# arduino_aprs_modem_-_corrected.net
KiCad netlist of a schematic drawn in EAGLE
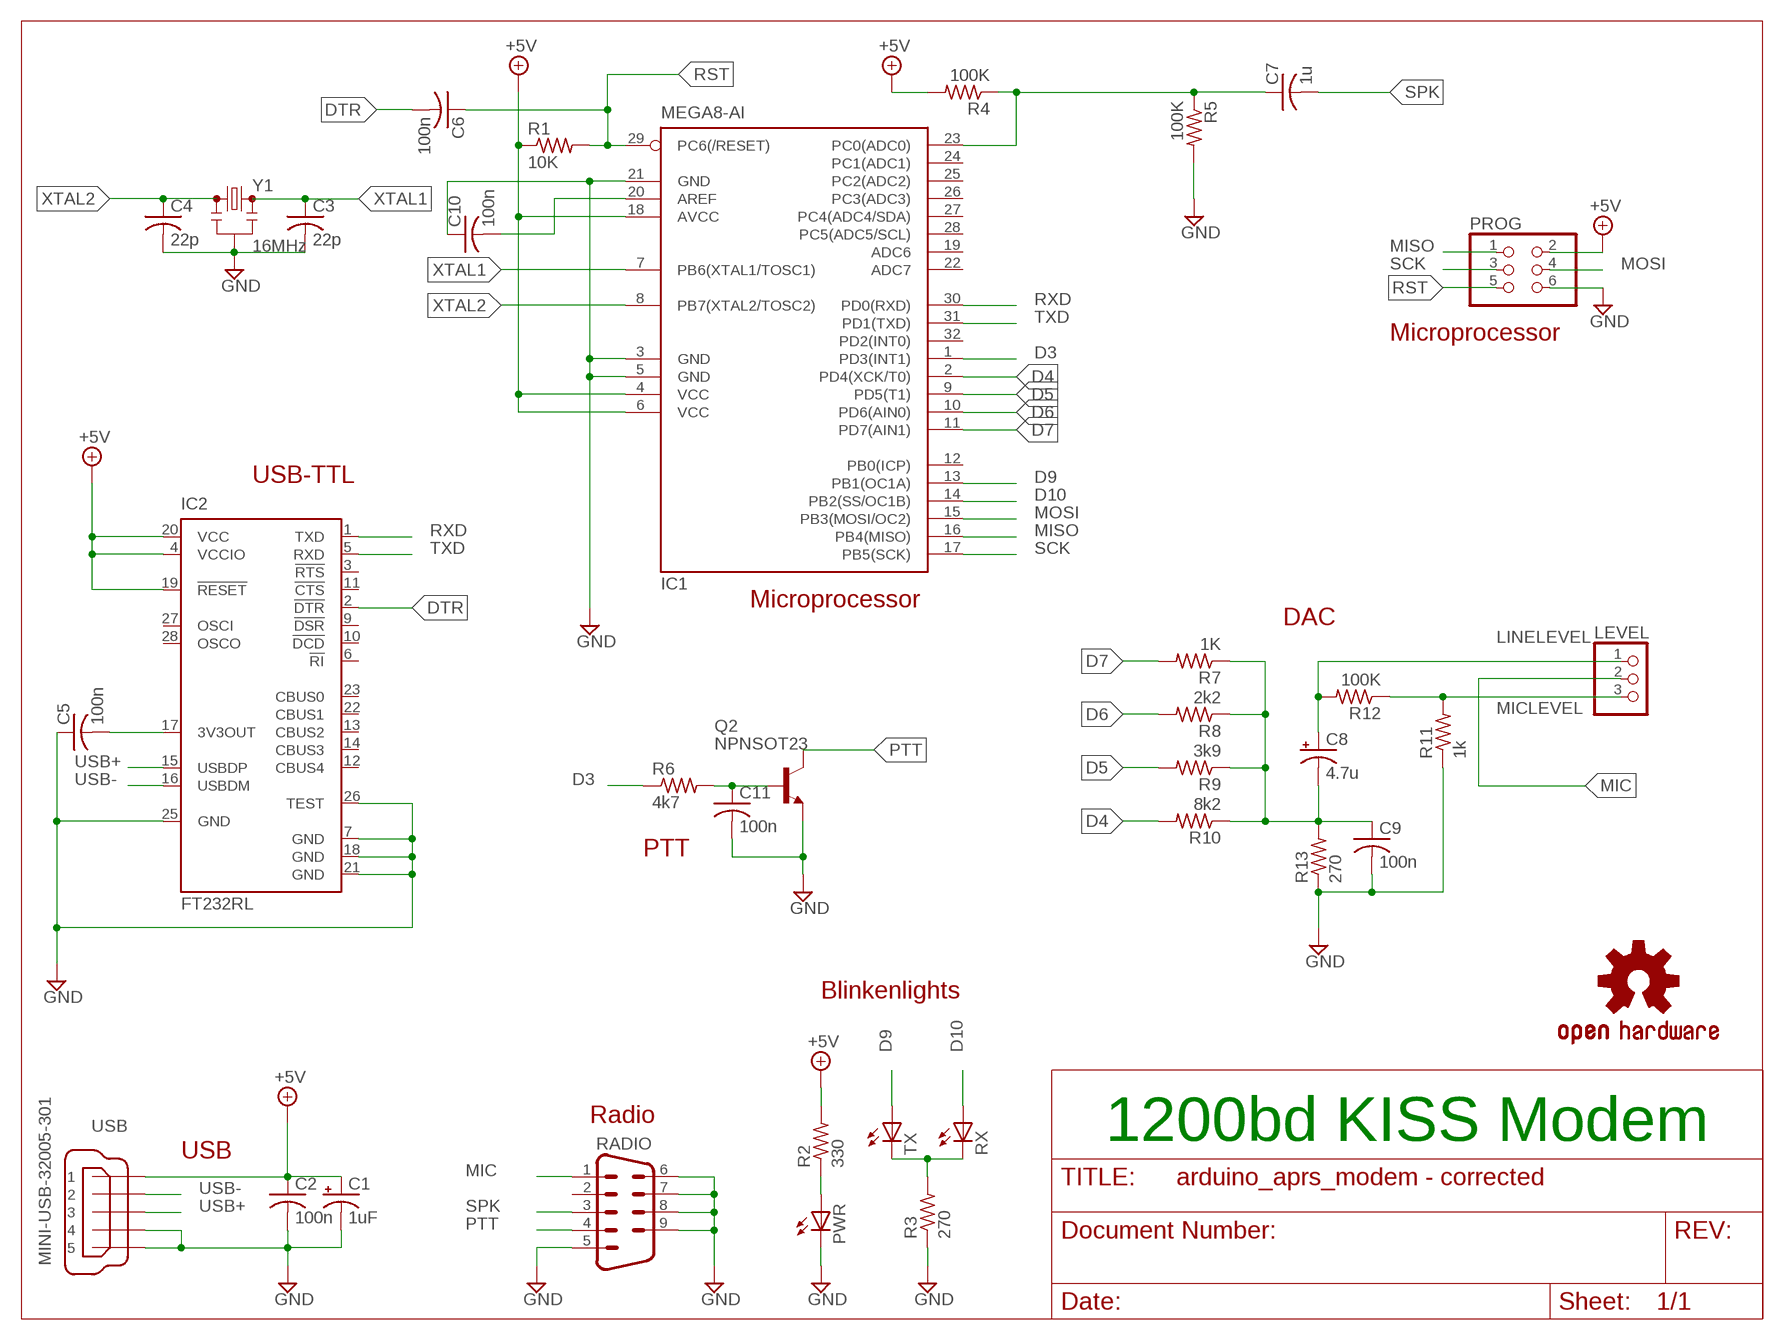
[diagram p0: schematic, sheet 1]

(export (version "E")
  (design (tool "Eeschema 10.0.6"))
  (components
    (comp (ref "C1")
      (value "1uF")
      (footprint "eagle-import:E2-5")
      (libsource (lib "eagle-import") (part "CPOL-USE2-5"))
    )
    (comp (ref "C2")
      (value "100n")
      (footprint "eagle-import:C0805")
      (libsource (lib "eagle-import") (part "C-USC0805"))
    )
    (comp (ref "C3")
      (value "22p")
      (footprint "eagle-import:C0805")
      (libsource (lib "eagle-import") (part "C-USC0805"))
    )
    (comp (ref "C4")
      (value "22p")
      (footprint "eagle-import:C0805")
      (libsource (lib "eagle-import") (part "C-USC0805"))
    )
    (comp (ref "C5")
      (value "100n")
      (footprint "eagle-import:C0805")
      (libsource (lib "eagle-import") (part "C-USC0805"))
    )
    (comp (ref "C6")
      (value "100n")
      (footprint "eagle-import:C0805")
      (libsource (lib "eagle-import") (part "C-USC0805"))
    )
    (comp (ref "C7")
      (value "1u")
      (footprint "eagle-import:C0805")
      (libsource (lib "eagle-import") (part "C-USC0805"))
    )
    (comp (ref "C8")
      (value "4.7u")
      (footprint "eagle-import:E2-5")
      (libsource (lib "eagle-import") (part "CPOL-USE2-5"))
    )
    (comp (ref "C9")
      (value "100n")
      (footprint "eagle-import:C0805")
      (libsource (lib "eagle-import") (part "C-USC0805"))
    )
    (comp (ref "C10")
      (value "100n")
      (footprint "eagle-import:C0805")
      (libsource (lib "eagle-import") (part "C-USC0805"))
    )
    (comp (ref "C11")
      (value "100n")
      (footprint "eagle-import:C0805")
      (libsource (lib "eagle-import") (part "C-USC0805"))
    )
    (comp (ref "IC1")
      (value "MEGA8-AI")
      (footprint "eagle-import:TQFP32-08")
      (fields (field (name "MPN") "ATMEGA8-16AU"))
      (libsource (lib "eagle-import") (part "MEGA8-AI"))
    )
    (comp (ref "IC2")
      (value "FT232RL")
      (footprint "eagle-import:SSOP28")
      (libsource (lib "eagle-import") (part "FT232RL"))
    )
    (comp (ref "LEVEL")
      (value "PINHD-1X3")
      (footprint "eagle-import:1X03")
      (libsource (lib "eagle-import") (part "PINHD-1X3"))
    )
    (comp (ref "PROG")
      (value "PINHD-2X3")
      (footprint "eagle-import:2X03")
      (libsource (lib "eagle-import") (part "PINHD-2X3"))
    )
    (comp (ref "PWR")
      (value "LEDCHIPLED_0805")
      (footprint "eagle-import:CHIPLED_0805")
      (libsource (lib "eagle-import") (part "LEDCHIPLED_0805"))
    )
    (comp (ref "Q2")
      (value "NPNSOT23")
      (footprint "eagle-import:SOT23")
      (libsource (lib "eagle-import") (part "NPNSOT23"))
    )
    (comp (ref "R1")
      (value "10K")
      (footprint "eagle-import:M0805")
      (libsource (lib "eagle-import") (part "R-US_M0805"))
    )
    (comp (ref "R2")
      (value "330")
      (footprint "eagle-import:M0805")
      (libsource (lib "eagle-import") (part "R-US_M0805"))
    )
    (comp (ref "R3")
      (value "270")
      (footprint "eagle-import:M0805")
      (libsource (lib "eagle-import") (part "R-US_M0805"))
    )
    (comp (ref "R4")
      (value "100K")
      (footprint "eagle-import:M0805")
      (libsource (lib "eagle-import") (part "R-US_M0805"))
    )
    (comp (ref "R5")
      (value "100K")
      (footprint "eagle-import:M0805")
      (libsource (lib "eagle-import") (part "R-US_M0805"))
    )
    (comp (ref "R6")
      (value "4k7")
      (footprint "eagle-import:M0805")
      (libsource (lib "eagle-import") (part "R-US_M0805"))
    )
    (comp (ref "R7")
      (value "1K")
      (footprint "eagle-import:M0805")
      (libsource (lib "eagle-import") (part "R-US_M0805"))
    )
    (comp (ref "R8")
      (value "2k2")
      (footprint "eagle-import:M0805")
      (libsource (lib "eagle-import") (part "R-US_M0805"))
    )
    (comp (ref "R9")
      (value "3k9")
      (footprint "eagle-import:M0805")
      (libsource (lib "eagle-import") (part "R-US_M0805"))
    )
    (comp (ref "R10")
      (value "8k2")
      (footprint "eagle-import:M0805")
      (libsource (lib "eagle-import") (part "R-US_M0805"))
    )
    (comp (ref "R11")
      (value "1k")
      (footprint "eagle-import:M0805")
      (libsource (lib "eagle-import") (part "R-US_M0805"))
    )
    (comp (ref "R12")
      (value "100K")
      (footprint "eagle-import:M0805")
      (libsource (lib "eagle-import") (part "R-US_M0805"))
    )
    (comp (ref "R13")
      (value "270")
      (footprint "eagle-import:M0805")
      (libsource (lib "eagle-import") (part "R-US_M0805"))
    )
    (comp (ref "RADIO")
      (value "M09H")
      (footprint "eagle-import:M09H")
      (libsource (lib "eagle-import") (part "M09H"))
    )
    (comp (ref "RX")
      (value "LEDCHIPLED_0805")
      (footprint "eagle-import:CHIPLED_0805")
      (libsource (lib "eagle-import") (part "LEDCHIPLED_0805"))
    )
    (comp (ref "TX")
      (value "LEDCHIPLED_0805")
      (footprint "eagle-import:CHIPLED_0805")
      (libsource (lib "eagle-import") (part "LEDCHIPLED_0805"))
    )
    (comp (ref "U$1")
      (value "OSHW-LOGOM")
      (footprint "eagle-import:OSHW-LOGO-M")
      (libsource (lib "eagle-import") (part "OSHW-LOGOM"))
    )
    (comp (ref "USB")
      (value "MINI-USB-32005-301")
      (footprint "eagle-import:32005-301")
      (libsource (lib "eagle-import") (part "MINI-USB-32005-301"))
    )
    (comp (ref "Y1")
      (value "16MHz")
      (footprint "eagle-import:RESONATOR-PTH")
      (libsource (lib "eagle-import") (part "RESONATORPTH"))
    )
  )
  (nets
    (net (code "1") (name "+5V") (class "Default")
      (node (ref "C1") (pin "+") (pinfunction "+_+") (pintype "passive"))
      (node (ref "C2") (pin "1") (pinfunction "1_1") (pintype "passive"))
      (node (ref "IC1") (pin "18") (pinfunction "AVCC_18") (pintype "power_in"))
      (node (ref "IC1") (pin "4") (pinfunction "VCC_4") (pintype "power_in"))
      (node (ref "IC1") (pin "6") (pinfunction "VCC_6") (pintype "power_in"))
      (node (ref "IC2") (pin "19") (pinfunction "~{RESET}_19") (pintype "input"))
      (node (ref "IC2") (pin "20") (pinfunction "VCC_20") (pintype "power_in"))
      (node (ref "IC2") (pin "4") (pinfunction "VCCIO_4") (pintype "power_in"))
      (node (ref "PROG") (pin "2") (pinfunction "2_2") (pintype "passive"))
      (node (ref "R1") (pin "1") (pinfunction "1_1") (pintype "passive"))
      (node (ref "R2") (pin "2") (pinfunction "2_2") (pintype "passive"))
      (node (ref "R4") (pin "2") (pinfunction "2_2") (pintype "passive"))
      (node (ref "USB") (pin "1") (pinfunction "1_1") (pintype "passive"))
    )
    (net (code "2") (name "/D3") (class "Default")
      (node (ref "IC1") (pin "1") (pinfunction "PD3(INT1)_1") (pintype "bidirectional"))
      (node (ref "R6") (pin "1") (pinfunction "1_1") (pintype "passive"))
    )
    (net (code "3") (name "/D9") (class "Default")
      (node (ref "IC1") (pin "13") (pinfunction "PB1(OC1A)_13") (pintype "bidirectional"))
      (node (ref "TX") (pin "A") (pinfunction "A_A") (pintype "passive"))
    )
    (net (code "4") (name "/D10") (class "Default")
      (node (ref "IC1") (pin "14") (pinfunction "PB2(SS/OC1B)_14") (pintype "bidirectional"))
      (node (ref "RX") (pin "A") (pinfunction "A_A") (pintype "passive"))
    )
    (net (code "5") (name "/LINELEVEL") (class "Default")
      (node (ref "C8") (pin "+") (pinfunction "+_+") (pintype "passive"))
      (node (ref "LEVEL") (pin "1") (pinfunction "1_1") (pintype "passive"))
      (node (ref "R12") (pin "2") (pinfunction "2_2") (pintype "passive"))
    )
    (net (code "6") (name "/MICLEVEL") (class "Default")
      (node (ref "LEVEL") (pin "3") (pinfunction "3_3") (pintype "passive"))
      (node (ref "R11") (pin "2") (pinfunction "2_2") (pintype "passive"))
      (node (ref "R12") (pin "1") (pinfunction "1_1") (pintype "passive"))
    )
    (net (code "7") (name "/MISO") (class "Default")
      (node (ref "IC1") (pin "16") (pinfunction "PB4(MISO)_16") (pintype "bidirectional"))
      (node (ref "PROG") (pin "1") (pinfunction "1_1") (pintype "passive"))
    )
    (net (code "8") (name "/MOSI") (class "Default")
      (node (ref "IC1") (pin "15") (pinfunction "PB3(MOSI/OC2)_15") (pintype "bidirectional"))
      (node (ref "PROG") (pin "4") (pinfunction "4_4") (pintype "passive"))
    )
    (net (code "9") (name "/RXD") (class "Default")
      (node (ref "IC1") (pin "30") (pinfunction "PD0(RXD)_30") (pintype "bidirectional"))
      (node (ref "IC2") (pin "1") (pinfunction "TXD_1") (pintype "output"))
    )
    (net (code "10") (name "/SCK") (class "Default")
      (node (ref "IC1") (pin "17") (pinfunction "PB5(SCK)_17") (pintype "bidirectional"))
      (node (ref "PROG") (pin "3") (pinfunction "3_3") (pintype "passive"))
    )
    (net (code "11") (name "/TXD") (class "Default")
      (node (ref "IC1") (pin "31") (pinfunction "PD1(TXD)_31") (pintype "bidirectional"))
      (node (ref "IC2") (pin "5") (pinfunction "RXD_5") (pintype "input"))
    )
    (net (code "12") (name "/USB+") (class "Default")
      (node (ref "IC2") (pin "15") (pinfunction "USBDP_15") (pintype "bidirectional"))
      (node (ref "USB") (pin "3") (pinfunction "3_3") (pintype "passive"))
    )
    (net (code "13") (name "/USB-") (class "Default")
      (node (ref "IC2") (pin "16") (pinfunction "USBDM_16") (pintype "bidirectional"))
      (node (ref "USB") (pin "2") (pinfunction "2_2") (pintype "passive"))
    )
    (net (code "14") (name "D4") (class "Default")
      (node (ref "IC1") (pin "2") (pinfunction "PD4(XCK/T0)_2") (pintype "bidirectional"))
      (node (ref "R10") (pin "2") (pinfunction "2_2") (pintype "passive"))
    )
    (net (code "15") (name "D5") (class "Default")
      (node (ref "IC1") (pin "9") (pinfunction "PD5(T1)_9") (pintype "bidirectional"))
      (node (ref "R9") (pin "2") (pinfunction "2_2") (pintype "passive"))
    )
    (net (code "16") (name "D6") (class "Default")
      (node (ref "IC1") (pin "10") (pinfunction "PD6(AIN0)_10") (pintype "bidirectional"))
      (node (ref "R8") (pin "2") (pinfunction "2_2") (pintype "passive"))
    )
    (net (code "17") (name "D7") (class "Default")
      (node (ref "IC1") (pin "11") (pinfunction "PD7(AIN1)_11") (pintype "bidirectional"))
      (node (ref "R7") (pin "2") (pinfunction "2_2") (pintype "passive"))
    )
    (net (code "18") (name "DTR") (class "Default")
      (node (ref "C6") (pin "2") (pinfunction "2_2") (pintype "passive"))
      (node (ref "IC2") (pin "2") (pinfunction "~{DTR}_2") (pintype "output"))
    )
    (net (code "19") (name "GND") (class "Default")
      (node (ref "C1") (pin "-") (pinfunction "-_-") (pintype "passive"))
      (node (ref "C10") (pin "1") (pinfunction "1_1") (pintype "passive"))
      (node (ref "C11") (pin "2") (pinfunction "2_2") (pintype "passive"))
      (node (ref "C2") (pin "2") (pinfunction "2_2") (pintype "passive"))
      (node (ref "C3") (pin "2") (pinfunction "2_2") (pintype "passive"))
      (node (ref "C4") (pin "2") (pinfunction "2_2") (pintype "passive"))
      (node (ref "C5") (pin "1") (pinfunction "1_1") (pintype "passive"))
      (node (ref "C9") (pin "2") (pinfunction "2_2") (pintype "passive"))
      (node (ref "IC1") (pin "21") (pinfunction "GND_21") (pintype "power_in"))
      (node (ref "IC1") (pin "3") (pinfunction "GND_3") (pintype "power_in"))
      (node (ref "IC1") (pin "5") (pinfunction "GND_5") (pintype "power_in"))
      (node (ref "IC2") (pin "18") (pinfunction "GND_18") (pintype "power_in"))
      (node (ref "IC2") (pin "21") (pinfunction "GND_21") (pintype "power_in"))
      (node (ref "IC2") (pin "25") (pinfunction "GND_25") (pintype "power_in"))
      (node (ref "IC2") (pin "26") (pinfunction "TEST_26") (pintype "input"))
      (node (ref "IC2") (pin "7") (pinfunction "GND_7") (pintype "power_in"))
      (node (ref "PROG") (pin "6") (pinfunction "6_6") (pintype "passive"))
      (node (ref "PWR") (pin "C") (pinfunction "C_C") (pintype "passive"))
      (node (ref "Q2") (pin "2") (pinfunction "E_2") (pintype "passive"))
      (node (ref "R11") (pin "1") (pinfunction "1_1") (pintype "passive"))
      (node (ref "R13") (pin "1") (pinfunction "1_1") (pintype "passive"))
      (node (ref "R3") (pin "1") (pinfunction "1_1") (pintype "passive"))
      (node (ref "R5") (pin "2") (pinfunction "2_2") (pintype "passive"))
      (node (ref "RADIO") (pin "5") (pinfunction "5_5") (pintype "passive"))
      (node (ref "RADIO") (pin "6") (pinfunction "6_6") (pintype "passive"))
      (node (ref "RADIO") (pin "7") (pinfunction "7_7") (pintype "passive"))
      (node (ref "RADIO") (pin "8") (pinfunction "8_8") (pintype "passive"))
      (node (ref "RADIO") (pin "9") (pinfunction "9_9") (pintype "passive"))
      (node (ref "USB") (pin "4") (pinfunction "4_4") (pintype "passive"))
      (node (ref "USB") (pin "5") (pinfunction "5_5") (pintype "passive"))
      (node (ref "Y1") (pin "2") (pinfunction "2_2") (pintype "passive"))
    )
    (net (code "20") (name "MIC") (class "Default")
      (node (ref "LEVEL") (pin "2") (pinfunction "2_2") (pintype "passive"))
      (node (ref "RADIO") (pin "1") (pinfunction "1_1") (pintype "passive"))
    )
    (net (code "21") (name "Net-(C8-Pad-)") (class "Default")
      (node (ref "C8") (pin "-") (pinfunction "-_-") (pintype "passive"))
      (node (ref "C9") (pin "1") (pinfunction "1_1") (pintype "passive"))
      (node (ref "R10") (pin "1") (pinfunction "1_1") (pintype "passive"))
      (node (ref "R13") (pin "2") (pinfunction "2_2") (pintype "passive"))
      (node (ref "R7") (pin "1") (pinfunction "1_1") (pintype "passive"))
      (node (ref "R8") (pin "1") (pinfunction "1_1") (pintype "passive"))
      (node (ref "R9") (pin "1") (pinfunction "1_1") (pintype "passive"))
    )
    (net (code "22") (name "Net-(IC1-AREF)") (class "Default")
      (node (ref "C10") (pin "2") (pinfunction "2_2") (pintype "passive"))
      (node (ref "IC1") (pin "20") (pinfunction "AREF_20") (pintype "passive"))
    )
    (net (code "23") (name "Net-(IC1-PC0(ADC0))") (class "Default")
      (node (ref "C7") (pin "1") (pinfunction "1_1") (pintype "passive"))
      (node (ref "IC1") (pin "23") (pinfunction "PC0(ADC0)_23") (pintype "bidirectional"))
      (node (ref "R4") (pin "1") (pinfunction "1_1") (pintype "passive"))
      (node (ref "R5") (pin "1") (pinfunction "1_1") (pintype "passive"))
    )
    (net (code "24") (name "Net-(IC2-3V3OUT)") (class "Default")
      (node (ref "C5") (pin "2") (pinfunction "2_2") (pintype "passive"))
      (node (ref "IC2") (pin "17") (pinfunction "3V3OUT_17") (pintype "output"))
    )
    (net (code "25") (name "Net-(PWR-PadA)") (class "Default")
      (node (ref "PWR") (pin "A") (pinfunction "A_A") (pintype "passive"))
      (node (ref "R2") (pin "1") (pinfunction "1_1") (pintype "passive"))
    )
    (net (code "26") (name "Net-(Q2-B)") (class "Default")
      (node (ref "C11") (pin "1") (pinfunction "1_1") (pintype "passive"))
      (node (ref "Q2") (pin "1") (pinfunction "B_1") (pintype "passive"))
      (node (ref "R6") (pin "2") (pinfunction "2_2") (pintype "passive"))
    )
    (net (code "27") (name "Net-(R3-Pad2)") (class "Default")
      (node (ref "R3") (pin "2") (pinfunction "2_2") (pintype "passive"))
      (node (ref "RX") (pin "C") (pinfunction "C_C") (pintype "passive"))
      (node (ref "TX") (pin "C") (pinfunction "C_C") (pintype "passive"))
    )
    (net (code "28") (name "PTT") (class "Default")
      (node (ref "Q2") (pin "3") (pinfunction "C_3") (pintype "passive"))
      (node (ref "RADIO") (pin "4") (pinfunction "4_4") (pintype "passive"))
    )
    (net (code "29") (name "RST") (class "Default")
      (node (ref "C6") (pin "1") (pinfunction "1_1") (pintype "passive"))
      (node (ref "IC1") (pin "29") (pinfunction "PC6(/RESET)_29") (pintype "bidirectional"))
      (node (ref "PROG") (pin "5") (pinfunction "5_5") (pintype "passive"))
      (node (ref "R1") (pin "2") (pinfunction "2_2") (pintype "passive"))
    )
    (net (code "30") (name "SPK") (class "Default")
      (node (ref "C7") (pin "2") (pinfunction "2_2") (pintype "passive"))
      (node (ref "RADIO") (pin "3") (pinfunction "3_3") (pintype "passive"))
    )
    (net (code "31") (name "XTAL1") (class "Default")
      (node (ref "C3") (pin "1") (pinfunction "1_1") (pintype "passive"))
      (node (ref "IC1") (pin "7") (pinfunction "PB6(XTAL1/TOSC1)_7") (pintype "bidirectional"))
      (node (ref "Y1") (pin "3") (pinfunction "3_3") (pintype "passive"))
    )
    (net (code "32") (name "XTAL2") (class "Default")
      (node (ref "C4") (pin "1") (pinfunction "1_1") (pintype "passive"))
      (node (ref "IC1") (pin "8") (pinfunction "PB7(XTAL2/TOSC2)_8") (pintype "bidirectional"))
      (node (ref "Y1") (pin "1") (pinfunction "1_1") (pintype "passive"))
    )
    (net (code "33") (name "unconnected-(IC1-ADC6-Pad19)") (class "Default")
      (node (ref "IC1") (pin "19") (pinfunction "ADC6_19") (pintype "bidirectional"))
    )
    (net (code "34") (name "unconnected-(IC1-ADC7-Pad22)") (class "Default")
      (node (ref "IC1") (pin "22") (pinfunction "ADC7_22") (pintype "bidirectional"))
    )
    (net (code "35") (name "unconnected-(IC1-PB0(ICP)-Pad12)") (class "Default")
      (node (ref "IC1") (pin "12") (pinfunction "PB0(ICP)_12") (pintype "bidirectional"))
    )
    (net (code "36") (name "unconnected-(IC1-PC1(ADC1)-Pad24)") (class "Default")
      (node (ref "IC1") (pin "24") (pinfunction "PC1(ADC1)_24") (pintype "bidirectional"))
    )
    (net (code "37") (name "unconnected-(IC1-PC2(ADC2)-Pad25)") (class "Default")
      (node (ref "IC1") (pin "25") (pinfunction "PC2(ADC2)_25") (pintype "bidirectional"))
    )
    (net (code "38") (name "unconnected-(IC1-PC3(ADC3)-Pad26)") (class "Default")
      (node (ref "IC1") (pin "26") (pinfunction "PC3(ADC3)_26") (pintype "bidirectional"))
    )
    (net (code "39") (name "unconnected-(IC1-PC4(ADC4{slash}SDA)-Pad27)") (class "Default")
      (node (ref "IC1") (pin "27") (pinfunction "PC4(ADC4/SDA)_27") (pintype "bidirectional"))
    )
    (net (code "40") (name "unconnected-(IC1-PC5(ADC5{slash}SCL)-Pad28)") (class "Default")
      (node (ref "IC1") (pin "28") (pinfunction "PC5(ADC5/SCL)_28") (pintype "bidirectional"))
    )
    (net (code "41") (name "unconnected-(IC1-PD2(INT0)-Pad32)") (class "Default")
      (node (ref "IC1") (pin "32") (pinfunction "PD2(INT0)_32") (pintype "bidirectional"))
    )
    (net (code "42") (name "unconnected-(IC2-CBUS0-Pad23)") (class "Default")
      (node (ref "IC2") (pin "23") (pinfunction "CBUS0_23") (pintype "bidirectional"))
    )
    (net (code "43") (name "unconnected-(IC2-CBUS1-Pad22)") (class "Default")
      (node (ref "IC2") (pin "22") (pinfunction "CBUS1_22") (pintype "bidirectional"))
    )
    (net (code "44") (name "unconnected-(IC2-CBUS2-Pad13)") (class "Default")
      (node (ref "IC2") (pin "13") (pinfunction "CBUS2_13") (pintype "bidirectional"))
    )
    (net (code "45") (name "unconnected-(IC2-CBUS3-Pad14)") (class "Default")
      (node (ref "IC2") (pin "14") (pinfunction "CBUS3_14") (pintype "bidirectional"))
    )
    (net (code "46") (name "unconnected-(IC2-CBUS4-Pad12)") (class "Default")
      (node (ref "IC2") (pin "12") (pinfunction "CBUS4_12") (pintype "bidirectional"))
    )
    (net (code "47") (name "unconnected-(IC2-OSCI-Pad27)") (class "Default")
      (node (ref "IC2") (pin "27") (pinfunction "OSCI_27") (pintype "input"))
    )
    (net (code "48") (name "unconnected-(IC2-OSCO-Pad28)") (class "Default")
      (node (ref "IC2") (pin "28") (pinfunction "OSCO_28") (pintype "output"))
    )
    (net (code "49") (name "unconnected-(IC2-~{CTS}-Pad11)") (class "Default")
      (node (ref "IC2") (pin "11") (pinfunction "~{CTS}_11") (pintype "input"))
    )
    (net (code "50") (name "unconnected-(IC2-~{DCD}-Pad10)") (class "Default")
      (node (ref "IC2") (pin "10") (pinfunction "~{DCD}_10") (pintype "input"))
    )
    (net (code "51") (name "unconnected-(IC2-~{DSR}-Pad9)") (class "Default")
      (node (ref "IC2") (pin "9") (pinfunction "~{DSR}_9") (pintype "input"))
    )
    (net (code "52") (name "unconnected-(IC2-~{RI}-Pad6)") (class "Default")
      (node (ref "IC2") (pin "6") (pinfunction "~{RI}_6") (pintype "input"))
    )
    (net (code "53") (name "unconnected-(IC2-~{RTS}-Pad3)") (class "Default")
      (node (ref "IC2") (pin "3") (pinfunction "~{RTS}_3") (pintype "output"))
    )
    (net (code "54") (name "unconnected-(RADIO-Pad2)") (class "Default")
      (node (ref "RADIO") (pin "2") (pinfunction "2_2") (pintype "passive"))
    )
  )
)
